# LM3914.net
KiCad netlist of a schematic drawn in EAGLE
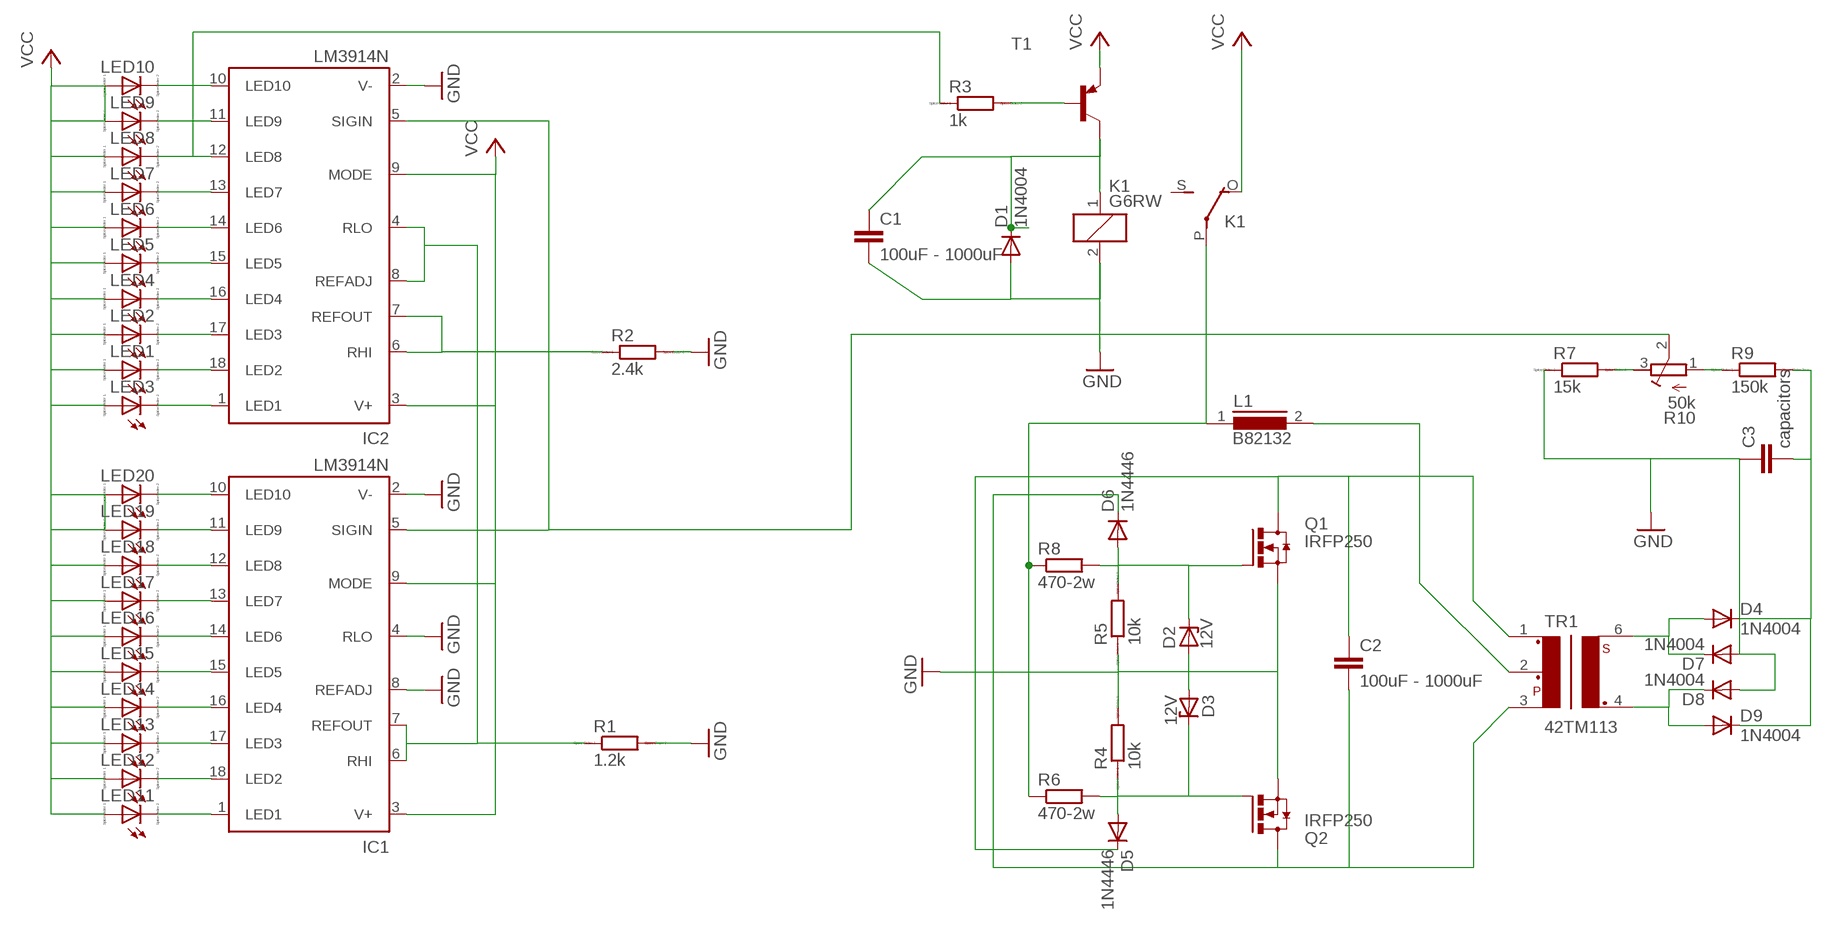
[diagram p0: schematic, sheet 1]

(export (version "E")
  (design (tool "Eeschema 10.0.6"))
  (components
    (comp (ref "C1")
      (value "100uF - 1000uF")
      (footprint "eagle-import:C2.5-3")
      (libsource (lib "eagle-import") (part "C2,5-3"))
    )
    (comp (ref "C2")
      (value "100uF - 1000uF")
      (footprint "eagle-import:C2.5-3")
      (libsource (lib "eagle-import") (part "C2,5-3"))
    )
    (comp (ref "C3")
      (value "capacitors")
      (footprint "eagle-import:C37.5B20")
      (libsource (lib "eagle-import") (part "C37/20"))
    )
    (comp (ref "D1")
      (value "1N4004")
      (footprint "eagle-import:DO41-10")
      (libsource (lib "eagle-import") (part "1N4004"))
    )
    (comp (ref "D2")
      (value "12V")
      (footprint "eagle-import:C1702-15")
      (libsource (lib "eagle-import") (part "ZENER-DIODEC1702-15"))
    )
    (comp (ref "D3")
      (value "12V")
      (footprint "eagle-import:C1702-15")
      (libsource (lib "eagle-import") (part "ZENER-DIODEC1702-15"))
    )
    (comp (ref "D4")
      (value "1N4004")
      (footprint "eagle-import:DO41-10")
      (libsource (lib "eagle-import") (part "1N4004"))
    )
    (comp (ref "D5")
      (value "1N4446")
      (footprint "eagle-import:DO35-10")
      (libsource (lib "eagle-import") (part "1N4446"))
    )
    (comp (ref "D6")
      (value "1N4446")
      (footprint "eagle-import:DO35-10")
      (libsource (lib "eagle-import") (part "1N4446"))
    )
    (comp (ref "D7")
      (value "1N4004")
      (footprint "eagle-import:DO41-10")
      (libsource (lib "eagle-import") (part "1N4004"))
    )
    (comp (ref "D8")
      (value "1N4004")
      (footprint "eagle-import:DO41-10")
      (libsource (lib "eagle-import") (part "1N4004"))
    )
    (comp (ref "D9")
      (value "1N4004")
      (footprint "eagle-import:DO41-10")
      (libsource (lib "eagle-import") (part "1N4004"))
    )
    (comp (ref "IC1")
      (value "LM3914N")
      (footprint "eagle-import:DIL18")
      (libsource (lib "eagle-import") (part "LM391N4"))
    )
    (comp (ref "IC2")
      (value "LM3914N")
      (footprint "eagle-import:DIL18")
      (libsource (lib "eagle-import") (part "LM391N4"))
    )
    (comp (ref "K1")
      (value "G6RW")
      (footprint "eagle-import:G6RW")
      (libsource (lib "eagle-import") (part "G6RW"))
    )
    (comp (ref "L1")
      (value "B82132")
      (footprint "eagle-import:SUKW2-22")
      (libsource (lib "eagle-import") (part "B82132"))
    )
    (comp (ref "LED1")
      (value "LED_ELD260")
      (footprint "eagle-import:LED_LD260")
      (libsource (lib "eagle-import") (part "LED_ELD260"))
    )
    (comp (ref "LED2")
      (value "LED_ELD260")
      (footprint "eagle-import:LED_LD260")
      (libsource (lib "eagle-import") (part "LED_ELD260"))
    )
    (comp (ref "LED3")
      (value "LED_ELD260")
      (footprint "eagle-import:LED_LD260")
      (libsource (lib "eagle-import") (part "LED_ELD260"))
    )
    (comp (ref "LED4")
      (value "LED_ELD260")
      (footprint "eagle-import:LED_LD260")
      (libsource (lib "eagle-import") (part "LED_ELD260"))
    )
    (comp (ref "LED5")
      (value "LED_ELD260")
      (footprint "eagle-import:LED_LD260")
      (libsource (lib "eagle-import") (part "LED_ELD260"))
    )
    (comp (ref "LED6")
      (value "LED_ELD260")
      (footprint "eagle-import:LED_LD260")
      (libsource (lib "eagle-import") (part "LED_ELD260"))
    )
    (comp (ref "LED7")
      (value "LED_ELD260")
      (footprint "eagle-import:LED_LD260")
      (libsource (lib "eagle-import") (part "LED_ELD260"))
    )
    (comp (ref "LED8")
      (value "LED_ELD260")
      (footprint "eagle-import:LED_LD260")
      (libsource (lib "eagle-import") (part "LED_ELD260"))
    )
    (comp (ref "LED9")
      (value "LED_ELD260")
      (footprint "eagle-import:LED_LD260")
      (libsource (lib "eagle-import") (part "LED_ELD260"))
    )
    (comp (ref "LED10")
      (value "LED_ELD260")
      (footprint "eagle-import:LED_LD260")
      (libsource (lib "eagle-import") (part "LED_ELD260"))
    )
    (comp (ref "LED11")
      (value "LED_ELD260")
      (footprint "eagle-import:LED_LD260")
      (libsource (lib "eagle-import") (part "LED_ELD260"))
    )
    (comp (ref "LED12")
      (value "LED_ELD260")
      (footprint "eagle-import:LED_LD260")
      (libsource (lib "eagle-import") (part "LED_ELD260"))
    )
    (comp (ref "LED13")
      (value "LED_ELD260")
      (footprint "eagle-import:LED_LD260")
      (libsource (lib "eagle-import") (part "LED_ELD260"))
    )
    (comp (ref "LED14")
      (value "LED_ELD260")
      (footprint "eagle-import:LED_LD260")
      (libsource (lib "eagle-import") (part "LED_ELD260"))
    )
    (comp (ref "LED15")
      (value "LED_ELD260")
      (footprint "eagle-import:LED_LD260")
      (libsource (lib "eagle-import") (part "LED_ELD260"))
    )
    (comp (ref "LED16")
      (value "LED_ELD260")
      (footprint "eagle-import:LED_LD260")
      (libsource (lib "eagle-import") (part "LED_ELD260"))
    )
    (comp (ref "LED17")
      (value "LED_ELD260")
      (footprint "eagle-import:LED_LD260")
      (libsource (lib "eagle-import") (part "LED_ELD260"))
    )
    (comp (ref "LED18")
      (value "LED_ELD260")
      (footprint "eagle-import:LED_LD260")
      (libsource (lib "eagle-import") (part "LED_ELD260"))
    )
    (comp (ref "LED19")
      (value "LED_ELD260")
      (footprint "eagle-import:LED_LD260")
      (libsource (lib "eagle-import") (part "LED_ELD260"))
    )
    (comp (ref "LED20")
      (value "LED_ELD260")
      (footprint "eagle-import:LED_LD260")
      (libsource (lib "eagle-import") (part "LED_ELD260"))
    )
    (comp (ref "Q1")
      (value "IRFP250")
      (footprint "eagle-import:TO-247AD-V")
      (libsource (lib "eagle-import") (part "IRFP250"))
    )
    (comp (ref "Q2")
      (value "IRFP250")
      (footprint "eagle-import:TO-247AD-V")
      (libsource (lib "eagle-import") (part "IRFP250"))
    )
    (comp (ref "R1")
      (value "1.2k")
      (footprint "eagle-import:0207_10")
      (libsource (lib "eagle-import") (part "R0207/10"))
    )
    (comp (ref "R2")
      (value "2.4k")
      (footprint "eagle-import:0207_10")
      (libsource (lib "eagle-import") (part "R0207/10"))
    )
    (comp (ref "R3")
      (value "1k")
      (footprint "eagle-import:0207_10")
      (libsource (lib "eagle-import") (part "R0207/10"))
    )
    (comp (ref "R4")
      (value "10k")
      (footprint "eagle-import:0207_10")
      (libsource (lib "eagle-import") (part "R0207/10"))
    )
    (comp (ref "R5")
      (value "10k")
      (footprint "eagle-import:0207_10")
      (libsource (lib "eagle-import") (part "R0207/10"))
    )
    (comp (ref "R6")
      (value "470-2w")
      (footprint "eagle-import:RDH_15")
      (libsource (lib "eagle-import") (part "R-EU_RDH/15"))
    )
    (comp (ref "R7")
      (value "15k")
      (footprint "eagle-import:0207_10")
      (libsource (lib "eagle-import") (part "R0207/10"))
    )
    (comp (ref "R8")
      (value "470-2w")
      (footprint "eagle-import:RDH_15")
      (libsource (lib "eagle-import") (part "R-EU_RDH/15"))
    )
    (comp (ref "R9")
      (value "150k")
      (footprint "eagle-import:0207_10")
      (libsource (lib "eagle-import") (part "R0207/10"))
    )
    (comp (ref "R10")
      (value "50k")
      (footprint "eagle-import:RTRIM64X")
      (libsource (lib "eagle-import") (part "R-TRIMM64X"))
    )
    (comp (ref "T1")
      (value "-PNP-TO220V")
      (footprint "eagle-import:TO220V")
      (libsource (lib "eagle-import") (part "-PNP-TO220V"))
    )
    (comp (ref "TR1")
      (value "42TM113")
      (footprint "eagle-import:42TM")
      (libsource (lib "eagle-import") (part "42TM113"))
    )
  )
  (nets
    (net (code "1") (name "GND") (class "Default")
      (node (ref "C1") (pin "2") (pinfunction "2_2") (pintype "passive"))
      (node (ref "C3") (pin "1") (pinfunction "1_1") (pintype "passive"))
      (node (ref "D1") (pin "A") (pinfunction "A_A") (pintype "passive"))
      (node (ref "D2") (pin "A") (pinfunction "A_A") (pintype "passive"))
      (node (ref "D3") (pin "A") (pinfunction "A_A") (pintype "passive"))
      (node (ref "D7") (pin "A") (pinfunction "A_A") (pintype "passive"))
      (node (ref "D8") (pin "A") (pinfunction "A_A") (pintype "passive"))
      (node (ref "IC1") (pin "2") (pinfunction "V-_2") (pintype "power_in"))
      (node (ref "IC1") (pin "4") (pinfunction "RLO_4") (pintype "input"))
      (node (ref "IC1") (pin "8") (pinfunction "REFADJ_8") (pintype "passive"))
      (node (ref "IC2") (pin "2") (pinfunction "V-_2") (pintype "power_in"))
      (node (ref "K1") (pin "2") (pinfunction "2_2") (pintype "passive"))
      (node (ref "Q1") (pin "S") (pinfunction "S_S") (pintype "passive"))
      (node (ref "Q2") (pin "S") (pinfunction "S_S") (pintype "passive"))
      (node (ref "R1") (pin "2") (pinfunction "2_2") (pintype "passive"))
      (node (ref "R2") (pin "2") (pinfunction "2_2") (pintype "passive"))
      (node (ref "R4") (pin "2") (pinfunction "2_2") (pintype "passive"))
      (node (ref "R5") (pin "1") (pinfunction "1_1") (pintype "passive"))
      (node (ref "R7") (pin "1") (pinfunction "1_1") (pintype "passive"))
    )
    (net (code "2") (name "Net-(C2-Pad1)") (class "Default")
      (node (ref "C2") (pin "1") (pinfunction "1_1") (pintype "passive"))
      (node (ref "D5") (pin "C") (pinfunction "C_C") (pintype "passive"))
      (node (ref "Q1") (pin "D") (pinfunction "D_D") (pintype "passive"))
      (node (ref "TR1") (pin "1") (pinfunction "1_1") (pintype "passive"))
    )
    (net (code "3") (name "Net-(C2-Pad2)") (class "Default")
      (node (ref "C2") (pin "2") (pinfunction "2_2") (pintype "passive"))
      (node (ref "D6") (pin "C") (pinfunction "C_C") (pintype "passive"))
      (node (ref "Q2") (pin "D") (pinfunction "D_D") (pintype "passive"))
      (node (ref "TR1") (pin "3") (pinfunction "3_3") (pintype "passive"))
    )
    (net (code "4") (name "Net-(C3-Pad2)") (class "Default")
      (node (ref "C3") (pin "2") (pinfunction "2_2") (pintype "passive"))
      (node (ref "D4") (pin "C") (pinfunction "C_C") (pintype "passive"))
      (node (ref "D9") (pin "C") (pinfunction "C_C") (pintype "passive"))
      (node (ref "R9") (pin "2") (pinfunction "2_2") (pintype "passive"))
    )
    (net (code "5") (name "Net-(D2-PadC)") (class "Default")
      (node (ref "D2") (pin "C") (pinfunction "C_C") (pintype "passive"))
      (node (ref "D6") (pin "A") (pinfunction "A_A") (pintype "passive"))
      (node (ref "Q1") (pin "G") (pinfunction "G_G") (pintype "passive"))
      (node (ref "R5") (pin "2") (pinfunction "2_2") (pintype "passive"))
      (node (ref "R8") (pin "2") (pinfunction "2_2") (pintype "passive"))
    )
    (net (code "6") (name "Net-(D3-PadC)") (class "Default")
      (node (ref "D3") (pin "C") (pinfunction "C_C") (pintype "passive"))
      (node (ref "D5") (pin "A") (pinfunction "A_A") (pintype "passive"))
      (node (ref "Q2") (pin "G") (pinfunction "G_G") (pintype "passive"))
      (node (ref "R4") (pin "1") (pinfunction "1_1") (pintype "passive"))
      (node (ref "R6") (pin "2") (pinfunction "2_2") (pintype "passive"))
    )
    (net (code "7") (name "Net-(D4-PadA)") (class "Default")
      (node (ref "D4") (pin "A") (pinfunction "A_A") (pintype "passive"))
      (node (ref "D7") (pin "C") (pinfunction "C_C") (pintype "passive"))
      (node (ref "TR1") (pin "6") (pinfunction "6_6") (pintype "passive"))
    )
    (net (code "8") (name "Net-(D8-PadC)") (class "Default")
      (node (ref "D8") (pin "C") (pinfunction "C_C") (pintype "passive"))
      (node (ref "D9") (pin "A") (pinfunction "A_A") (pintype "passive"))
      (node (ref "TR1") (pin "4") (pinfunction "4_4") (pintype "passive"))
    )
    (net (code "9") (name "Net-(IC1-LED1)") (class "Default")
      (node (ref "IC1") (pin "1") (pinfunction "LED1_1") (pintype "output"))
      (node (ref "LED11") (pin "K") (pinfunction "C_K") (pintype "passive"))
    )
    (net (code "10") (name "Net-(IC1-LED2)") (class "Default")
      (node (ref "IC1") (pin "18") (pinfunction "LED2_18") (pintype "output"))
      (node (ref "LED12") (pin "K") (pinfunction "C_K") (pintype "passive"))
    )
    (net (code "11") (name "Net-(IC1-LED3)") (class "Default")
      (node (ref "IC1") (pin "17") (pinfunction "LED3_17") (pintype "output"))
      (node (ref "LED13") (pin "K") (pinfunction "C_K") (pintype "passive"))
    )
    (net (code "12") (name "Net-(IC1-LED4)") (class "Default")
      (node (ref "IC1") (pin "16") (pinfunction "LED4_16") (pintype "output"))
      (node (ref "LED14") (pin "K") (pinfunction "C_K") (pintype "passive"))
    )
    (net (code "13") (name "Net-(IC1-LED5)") (class "Default")
      (node (ref "IC1") (pin "15") (pinfunction "LED5_15") (pintype "output"))
      (node (ref "LED15") (pin "K") (pinfunction "C_K") (pintype "passive"))
    )
    (net (code "14") (name "Net-(IC1-LED6)") (class "Default")
      (node (ref "IC1") (pin "14") (pinfunction "LED6_14") (pintype "output"))
      (node (ref "LED16") (pin "K") (pinfunction "C_K") (pintype "passive"))
    )
    (net (code "15") (name "Net-(IC1-LED7)") (class "Default")
      (node (ref "IC1") (pin "13") (pinfunction "LED7_13") (pintype "output"))
      (node (ref "LED17") (pin "K") (pinfunction "C_K") (pintype "passive"))
    )
    (net (code "16") (name "Net-(IC1-LED8)") (class "Default")
      (node (ref "IC1") (pin "12") (pinfunction "LED8_12") (pintype "output"))
      (node (ref "LED18") (pin "K") (pinfunction "C_K") (pintype "passive"))
    )
    (net (code "17") (name "Net-(IC1-LED9)") (class "Default")
      (node (ref "IC1") (pin "11") (pinfunction "LED9_11") (pintype "output"))
      (node (ref "LED19") (pin "K") (pinfunction "C_K") (pintype "passive"))
    )
    (net (code "18") (name "Net-(IC1-LED10)") (class "Default")
      (node (ref "IC1") (pin "10") (pinfunction "LED10_10") (pintype "output"))
      (node (ref "LED20") (pin "K") (pinfunction "C_K") (pintype "passive"))
    )
    (net (code "19") (name "Net-(IC1-REFOUT)") (class "Default")
      (node (ref "IC1") (pin "6") (pinfunction "RHI_6") (pintype "input"))
      (node (ref "IC1") (pin "7") (pinfunction "REFOUT_7") (pintype "output"))
      (node (ref "IC2") (pin "4") (pinfunction "RLO_4") (pintype "input"))
      (node (ref "IC2") (pin "8") (pinfunction "REFADJ_8") (pintype "passive"))
      (node (ref "R1") (pin "1") (pinfunction "1_1") (pintype "passive"))
    )
    (net (code "20") (name "Net-(IC1-SIGIN)") (class "Default")
      (node (ref "IC1") (pin "5") (pinfunction "SIGIN_5") (pintype "input"))
      (node (ref "IC2") (pin "5") (pinfunction "SIGIN_5") (pintype "input"))
      (node (ref "R10") (pin "2") (pinfunction "S_2") (pintype "passive"))
    )
    (net (code "21") (name "Net-(IC2-LED1)") (class "Default")
      (node (ref "IC2") (pin "1") (pinfunction "LED1_1") (pintype "output"))
      (node (ref "LED3") (pin "K") (pinfunction "C_K") (pintype "passive"))
    )
    (net (code "22") (name "Net-(IC2-LED2)") (class "Default")
      (node (ref "IC2") (pin "18") (pinfunction "LED2_18") (pintype "output"))
      (node (ref "LED1") (pin "K") (pinfunction "C_K") (pintype "passive"))
    )
    (net (code "23") (name "Net-(IC2-LED3)") (class "Default")
      (node (ref "IC2") (pin "17") (pinfunction "LED3_17") (pintype "output"))
      (node (ref "LED2") (pin "K") (pinfunction "C_K") (pintype "passive"))
    )
    (net (code "24") (name "Net-(IC2-LED4)") (class "Default")
      (node (ref "IC2") (pin "16") (pinfunction "LED4_16") (pintype "output"))
      (node (ref "LED4") (pin "K") (pinfunction "C_K") (pintype "passive"))
    )
    (net (code "25") (name "Net-(IC2-LED5)") (class "Default")
      (node (ref "IC2") (pin "15") (pinfunction "LED5_15") (pintype "output"))
      (node (ref "LED5") (pin "K") (pinfunction "C_K") (pintype "passive"))
    )
    (net (code "26") (name "Net-(IC2-LED6)") (class "Default")
      (node (ref "IC2") (pin "14") (pinfunction "LED6_14") (pintype "output"))
      (node (ref "LED6") (pin "K") (pinfunction "C_K") (pintype "passive"))
    )
    (net (code "27") (name "Net-(IC2-LED7)") (class "Default")
      (node (ref "IC2") (pin "13") (pinfunction "LED7_13") (pintype "output"))
      (node (ref "LED7") (pin "K") (pinfunction "C_K") (pintype "passive"))
    )
    (net (code "28") (name "Net-(IC2-LED8)") (class "Default")
      (node (ref "IC2") (pin "12") (pinfunction "LED8_12") (pintype "output"))
      (node (ref "LED8") (pin "K") (pinfunction "C_K") (pintype "passive"))
      (node (ref "R3") (pin "1") (pinfunction "1_1") (pintype "passive"))
    )
    (net (code "29") (name "Net-(IC2-LED9)") (class "Default")
      (node (ref "IC2") (pin "11") (pinfunction "LED9_11") (pintype "output"))
      (node (ref "LED9") (pin "K") (pinfunction "C_K") (pintype "passive"))
    )
    (net (code "30") (name "Net-(IC2-LED10)") (class "Default")
      (node (ref "IC2") (pin "10") (pinfunction "LED10_10") (pintype "output"))
      (node (ref "LED10") (pin "K") (pinfunction "C_K") (pintype "passive"))
    )
    (net (code "31") (name "Net-(IC2-REFOUT)") (class "Default")
      (node (ref "IC2") (pin "6") (pinfunction "RHI_6") (pintype "input"))
      (node (ref "IC2") (pin "7") (pinfunction "REFOUT_7") (pintype "output"))
      (node (ref "R2") (pin "1") (pinfunction "1_1") (pintype "passive"))
    )
    (net (code "32") (name "Net-(K1-PadP)") (class "Default")
      (node (ref "K1") (pin "P") (pinfunction "P_P") (pintype "passive"))
      (node (ref "L1") (pin "1") (pinfunction "1_1") (pintype "passive"))
      (node (ref "R6") (pin "1") (pinfunction "1_1") (pintype "passive"))
      (node (ref "R8") (pin "1") (pinfunction "1_1") (pintype "passive"))
    )
    (net (code "33") (name "Net-(L1-Pad2)") (class "Default")
      (node (ref "L1") (pin "2") (pinfunction "2_2") (pintype "passive"))
      (node (ref "TR1") (pin "2") (pinfunction "2_2") (pintype "passive"))
    )
    (net (code "34") (name "Net-(R10-A)") (class "Default")
      (node (ref "R10") (pin "1") (pinfunction "A_1") (pintype "passive"))
      (node (ref "R9") (pin "1") (pinfunction "1_1") (pintype "passive"))
    )
    (net (code "35") (name "Net-(R10-E)") (class "Default")
      (node (ref "R10") (pin "3") (pinfunction "E_3") (pintype "passive"))
      (node (ref "R7") (pin "2") (pinfunction "2_2") (pintype "passive"))
    )
    (net (code "36") (name "Net-(T1-B)") (class "Default")
      (node (ref "R3") (pin "2") (pinfunction "2_2") (pintype "passive"))
      (node (ref "T1") (pin "1") (pinfunction "B_1") (pintype "passive"))
    )
    (net (code "37") (name "Net-(T1-C)") (class "Default")
      (node (ref "C1") (pin "1") (pinfunction "1_1") (pintype "passive"))
      (node (ref "D1") (pin "C") (pinfunction "C_C") (pintype "passive"))
      (node (ref "K1") (pin "1") (pinfunction "1_1") (pintype "passive"))
      (node (ref "T1") (pin "2") (pinfunction "C_2") (pintype "passive"))
    )
    (net (code "38") (name "VCC") (class "Default")
      (node (ref "IC1") (pin "3") (pinfunction "V+_3") (pintype "power_in"))
      (node (ref "IC1") (pin "9") (pinfunction "MODE_9") (pintype "input"))
      (node (ref "IC2") (pin "3") (pinfunction "V+_3") (pintype "power_in"))
      (node (ref "IC2") (pin "9") (pinfunction "MODE_9") (pintype "input"))
      (node (ref "K1") (pin "O") (pinfunction "O_O") (pintype "passive"))
      (node (ref "LED1") (pin "A") (pinfunction "A_A") (pintype "passive"))
      (node (ref "LED10") (pin "A") (pinfunction "A_A") (pintype "passive"))
      (node (ref "LED11") (pin "A") (pinfunction "A_A") (pintype "passive"))
      (node (ref "LED12") (pin "A") (pinfunction "A_A") (pintype "passive"))
      (node (ref "LED13") (pin "A") (pinfunction "A_A") (pintype "passive"))
      (node (ref "LED14") (pin "A") (pinfunction "A_A") (pintype "passive"))
      (node (ref "LED15") (pin "A") (pinfunction "A_A") (pintype "passive"))
      (node (ref "LED16") (pin "A") (pinfunction "A_A") (pintype "passive"))
      (node (ref "LED17") (pin "A") (pinfunction "A_A") (pintype "passive"))
      (node (ref "LED18") (pin "A") (pinfunction "A_A") (pintype "passive"))
      (node (ref "LED19") (pin "A") (pinfunction "A_A") (pintype "passive"))
      (node (ref "LED2") (pin "A") (pinfunction "A_A") (pintype "passive"))
      (node (ref "LED20") (pin "A") (pinfunction "A_A") (pintype "passive"))
      (node (ref "LED3") (pin "A") (pinfunction "A_A") (pintype "passive"))
      (node (ref "LED4") (pin "A") (pinfunction "A_A") (pintype "passive"))
      (node (ref "LED5") (pin "A") (pinfunction "A_A") (pintype "passive"))
      (node (ref "LED6") (pin "A") (pinfunction "A_A") (pintype "passive"))
      (node (ref "LED7") (pin "A") (pinfunction "A_A") (pintype "passive"))
      (node (ref "LED8") (pin "A") (pinfunction "A_A") (pintype "passive"))
      (node (ref "LED9") (pin "A") (pinfunction "A_A") (pintype "passive"))
      (node (ref "T1") (pin "3") (pinfunction "E_3") (pintype "passive"))
    )
    (net (code "39") (name "unconnected-(K1-PadS)") (class "Default")
      (node (ref "K1") (pin "S") (pinfunction "S_S") (pintype "passive"))
    )
  )
)
